# 503-WS2811-Multi_RV100.net
KiCad netlist of a schematic drawn in EAGLE
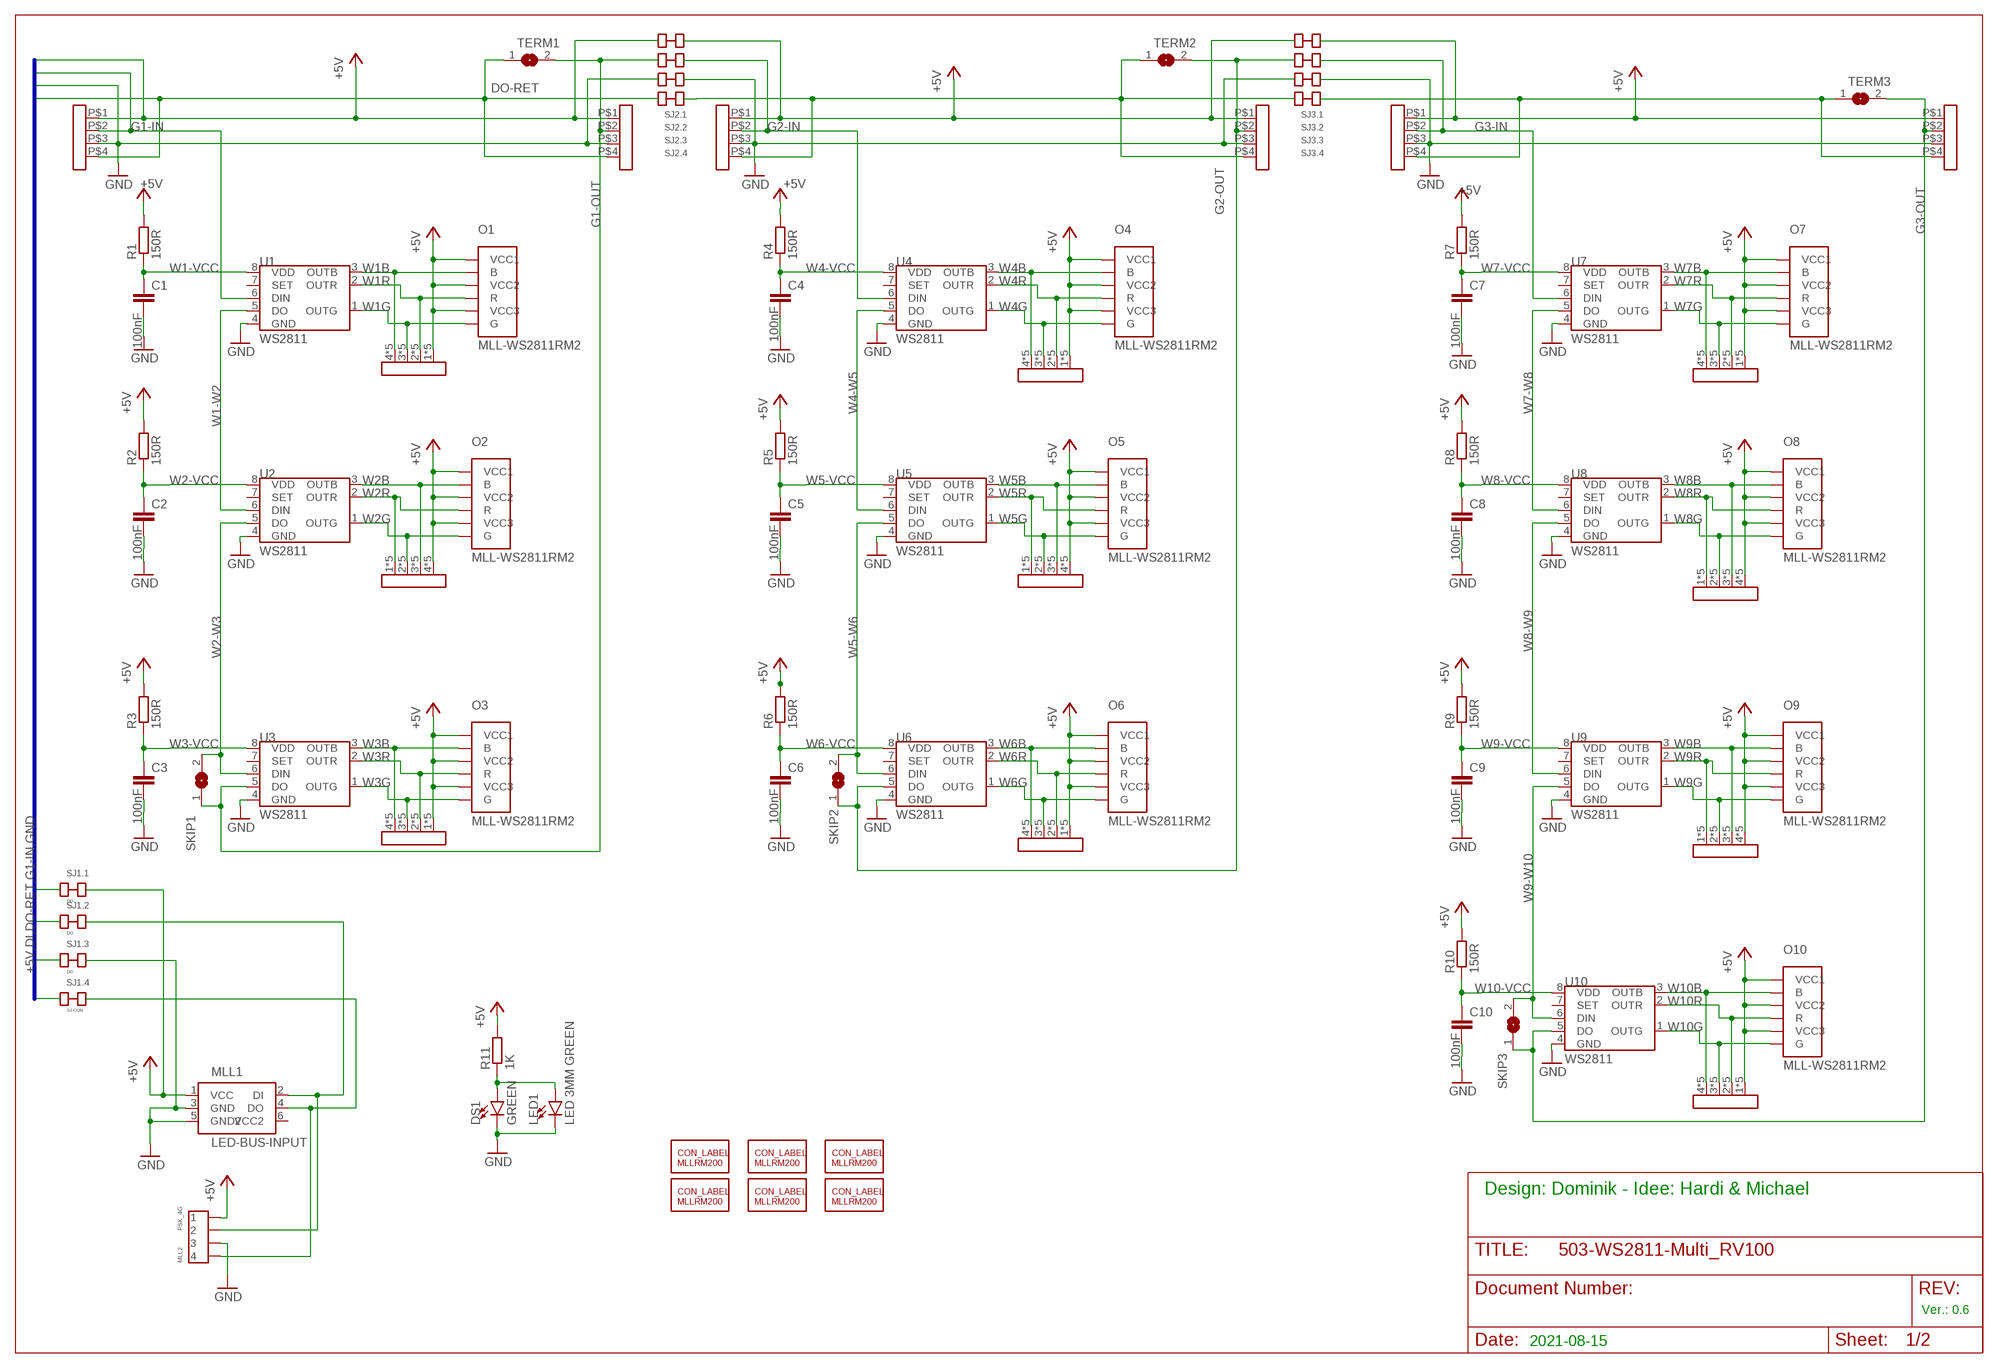
[diagram p0: schematic, sheet 1]
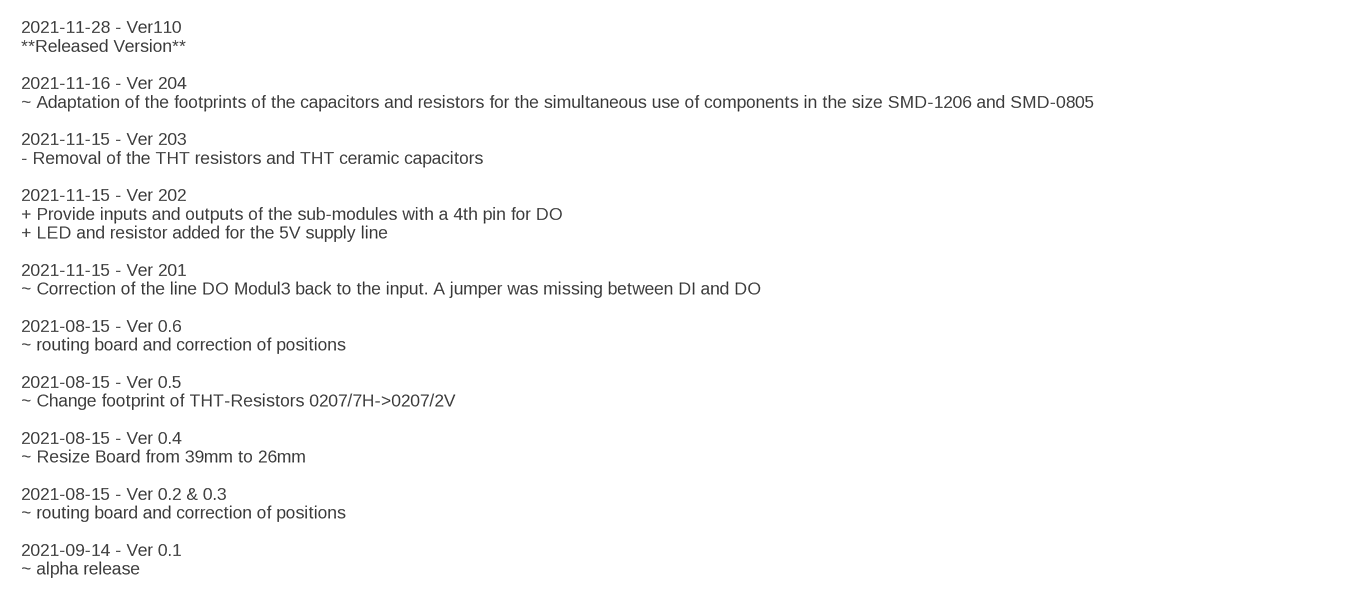
[diagram p1: schematic, sheet 2]

(export (version "E")
  (design (tool "Eeschema 10.0.6"))
  (components
    (comp (ref "C1")
      (value "100nF")
      (footprint "eagle-import:C1206")
      (libsource (lib "eagle-import") (part "C-EUC1206"))
    )
    (comp (ref "C2")
      (value "100nF")
      (footprint "eagle-import:C1206")
      (libsource (lib "eagle-import") (part "C-EUC1206"))
    )
    (comp (ref "C3")
      (value "100nF")
      (footprint "eagle-import:C1206")
      (libsource (lib "eagle-import") (part "C-EUC1206"))
    )
    (comp (ref "C4")
      (value "100nF")
      (footprint "eagle-import:C1206")
      (libsource (lib "eagle-import") (part "C-EUC1206"))
    )
    (comp (ref "C5")
      (value "100nF")
      (footprint "eagle-import:C1206")
      (libsource (lib "eagle-import") (part "C-EUC1206"))
    )
    (comp (ref "C6")
      (value "100nF")
      (footprint "eagle-import:C1206")
      (libsource (lib "eagle-import") (part "C-EUC1206"))
    )
    (comp (ref "C7")
      (value "100nF")
      (footprint "eagle-import:C1206")
      (libsource (lib "eagle-import") (part "C-EUC1206"))
    )
    (comp (ref "C8")
      (value "100nF")
      (footprint "eagle-import:C1206")
      (libsource (lib "eagle-import") (part "C-EUC1206"))
    )
    (comp (ref "C9")
      (value "100nF")
      (footprint "eagle-import:C1206")
      (libsource (lib "eagle-import") (part "C-EUC1206"))
    )
    (comp (ref "C10")
      (value "100nF")
      (footprint "eagle-import:C1206")
      (libsource (lib "eagle-import") (part "C-EUC1206"))
    )
    (comp (ref "DS1")
      (value "GREEN")
      (footprint "eagle-import:LED-1206")
      (libsource (lib "eagle-import") (part "LED-GREEN1206"))
    )
    (comp (ref "IN")
      (value "4XRM254")
      (footprint "eagle-import:4XRM254")
      (libsource (lib "eagle-import") (part "4XRM254"))
    )
    (comp (ref "LED1")
      (value "LED 3MM GREEN")
      (footprint "eagle-import:LED_3MM")
      (libsource (lib "eagle-import") (part "LED3MM"))
    )
    (comp (ref "M1_IN")
      (value "4XRM254")
      (footprint "eagle-import:4XRM254")
      (libsource (lib "eagle-import") (part "4XRM254"))
    )
    (comp (ref "M1_OUT")
      (value "4XRM254")
      (footprint "eagle-import:4XRM254")
      (libsource (lib "eagle-import") (part "4XRM254"))
    )
    (comp (ref "M2_IN")
      (value "4XRM254")
      (footprint "eagle-import:4XRM254")
      (libsource (lib "eagle-import") (part "4XRM254"))
    )
    (comp (ref "M2_OUT")
      (value "4XRM254")
      (footprint "eagle-import:4XRM254")
      (libsource (lib "eagle-import") (part "4XRM254"))
    )
    (comp (ref "MLL1")
      (value "LED-BUS-INPUT")
      (footprint "eagle-import:IDC6")
      (libsource (lib "eagle-import") (part "LED-BUS-INPUT"))
    )
    (comp (ref "MLL2")
      (value "PSK_4G")
      (footprint "eagle-import:PSSG4")
      (libsource (lib "eagle-import") (part "PSK_4G"))
    )
    (comp (ref "O1")
      (value "MLL-WS2811RM2")
      (footprint "eagle-import:MLL-WS2811-RM2")
      (libsource (lib "eagle-import") (part "MLL-WS2811RM2"))
    )
    (comp (ref "O2")
      (value "MLL-WS2811RM2")
      (footprint "eagle-import:MLL-WS2811-RM2")
      (libsource (lib "eagle-import") (part "MLL-WS2811RM2"))
    )
    (comp (ref "O3")
      (value "MLL-WS2811RM2")
      (footprint "eagle-import:MLL-WS2811-RM2")
      (libsource (lib "eagle-import") (part "MLL-WS2811RM2"))
    )
    (comp (ref "O4")
      (value "MLL-WS2811RM2")
      (footprint "eagle-import:MLL-WS2811-RM2")
      (libsource (lib "eagle-import") (part "MLL-WS2811RM2"))
    )
    (comp (ref "O5")
      (value "MLL-WS2811RM2")
      (footprint "eagle-import:MLL-WS2811-RM2")
      (libsource (lib "eagle-import") (part "MLL-WS2811RM2"))
    )
    (comp (ref "O6")
      (value "MLL-WS2811RM2")
      (footprint "eagle-import:MLL-WS2811-RM2")
      (libsource (lib "eagle-import") (part "MLL-WS2811RM2"))
    )
    (comp (ref "O7")
      (value "MLL-WS2811RM2")
      (footprint "eagle-import:MLL-WS2811-RM2")
      (libsource (lib "eagle-import") (part "MLL-WS2811RM2"))
    )
    (comp (ref "O8")
      (value "MLL-WS2811RM2")
      (footprint "eagle-import:MLL-WS2811-RM2")
      (libsource (lib "eagle-import") (part "MLL-WS2811RM2"))
    )
    (comp (ref "O9")
      (value "MLL-WS2811RM2")
      (footprint "eagle-import:MLL-WS2811-RM2")
      (libsource (lib "eagle-import") (part "MLL-WS2811RM2"))
    )
    (comp (ref "O10")
      (value "MLL-WS2811RM2")
      (footprint "eagle-import:MLL-WS2811-RM2")
      (libsource (lib "eagle-import") (part "MLL-WS2811RM2"))
    )
    (comp (ref "OUT")
      (value "4XRM254")
      (footprint "eagle-import:4XRM254")
      (libsource (lib "eagle-import") (part "4XRM254"))
    )
    (comp (ref "R1")
      (value "150R")
      (footprint "eagle-import:R1206")
      (libsource (lib "eagle-import") (part "R-EU_R1206"))
    )
    (comp (ref "R2")
      (value "150R")
      (footprint "eagle-import:R1206")
      (libsource (lib "eagle-import") (part "R-EU_R1206"))
    )
    (comp (ref "R3")
      (value "150R")
      (footprint "eagle-import:R1206")
      (libsource (lib "eagle-import") (part "R-EU_R1206"))
    )
    (comp (ref "R4")
      (value "150R")
      (footprint "eagle-import:R1206")
      (libsource (lib "eagle-import") (part "R-EU_R1206"))
    )
    (comp (ref "R5")
      (value "150R")
      (footprint "eagle-import:R1206")
      (libsource (lib "eagle-import") (part "R-EU_R1206"))
    )
    (comp (ref "R6")
      (value "150R")
      (footprint "eagle-import:R1206")
      (libsource (lib "eagle-import") (part "R-EU_R1206"))
    )
    (comp (ref "R7")
      (value "150R")
      (footprint "eagle-import:R1206")
      (libsource (lib "eagle-import") (part "R-EU_R1206"))
    )
    (comp (ref "R8")
      (value "150R")
      (footprint "eagle-import:R1206")
      (libsource (lib "eagle-import") (part "R-EU_R1206"))
    )
    (comp (ref "R9")
      (value "150R")
      (footprint "eagle-import:R1206")
      (libsource (lib "eagle-import") (part "R-EU_R1206"))
    )
    (comp (ref "R10")
      (value "150R")
      (footprint "eagle-import:R1206")
      (libsource (lib "eagle-import") (part "R-EU_R1206"))
    )
    (comp (ref "R11")
      (value "1K")
      (footprint "eagle-import:R1206")
      (libsource (lib "eagle-import") (part "R-EU_R1206"))
    )
    (comp (ref "SJ1.1")
      (value "DO")
      (footprint "eagle-import:SJ-CON")
      (libsource (lib "eagle-import") (part "SJ-CON"))
    )
    (comp (ref "SJ1.2")
      (value "DO")
      (footprint "eagle-import:SJ-CON")
      (libsource (lib "eagle-import") (part "SJ-CON"))
    )
    (comp (ref "SJ1.3")
      (value "DO")
      (footprint "eagle-import:SJ-CON")
      (libsource (lib "eagle-import") (part "SJ-CON"))
    )
    (comp (ref "SJ1.4")
      (value "SJ-CON")
      (footprint "eagle-import:SJ-CON")
      (libsource (lib "eagle-import") (part "SJ-CON"))
    )
    (comp (ref "SJ2.1")
      (value "SJ-CON")
      (footprint "eagle-import:SJ-CON")
      (libsource (lib "eagle-import") (part "SJ-CON"))
    )
    (comp (ref "SJ2.2")
      (value "SJ-CON")
      (footprint "eagle-import:SJ-CON")
      (libsource (lib "eagle-import") (part "SJ-CON"))
    )
    (comp (ref "SJ2.3")
      (value "SJ-CON")
      (footprint "eagle-import:SJ-CON")
      (libsource (lib "eagle-import") (part "SJ-CON"))
    )
    (comp (ref "SJ2.4")
      (value "SJ-CON")
      (footprint "eagle-import:SJ-CON")
      (libsource (lib "eagle-import") (part "SJ-CON"))
    )
    (comp (ref "SJ3.1")
      (value "SJ-CON")
      (footprint "eagle-import:SJ-CON")
      (libsource (lib "eagle-import") (part "SJ-CON"))
    )
    (comp (ref "SJ3.2")
      (value "SJ-CON")
      (footprint "eagle-import:SJ-CON")
      (libsource (lib "eagle-import") (part "SJ-CON"))
    )
    (comp (ref "SJ3.3")
      (value "SJ-CON")
      (footprint "eagle-import:SJ-CON")
      (libsource (lib "eagle-import") (part "SJ-CON"))
    )
    (comp (ref "SJ3.4")
      (value "SJ-CON")
      (footprint "eagle-import:SJ-CON")
      (libsource (lib "eagle-import") (part "SJ-CON"))
    )
    (comp (ref "SKIP1")
      (value "SJ")
      (footprint "eagle-import:SJ")
      (libsource (lib "eagle-import") (part "SJ"))
    )
    (comp (ref "SKIP2")
      (value "SJ")
      (footprint "eagle-import:SJ")
      (libsource (lib "eagle-import") (part "SJ"))
    )
    (comp (ref "SKIP3")
      (value "SJ")
      (footprint "eagle-import:SJ")
      (libsource (lib "eagle-import") (part "SJ"))
    )
    (comp (ref "TERM1")
      (value "SJ")
      (footprint "eagle-import:SJ")
      (libsource (lib "eagle-import") (part "SJ"))
    )
    (comp (ref "TERM2")
      (value "SJ")
      (footprint "eagle-import:SJ")
      (libsource (lib "eagle-import") (part "SJ"))
    )
    (comp (ref "TERM3")
      (value "SJ")
      (footprint "eagle-import:SJ")
      (libsource (lib "eagle-import") (part "SJ"))
    )
    (comp (ref "U$1")
      (value "CON-LABEL_MLLRM200_2RGB_M")
      (footprint "eagle-import:CON-LABEL_MLLRM200_RGB_M")
      (libsource (lib "eagle-import") (part "CON-LABEL_MLLRM200_2RGB_M"))
    )
    (comp (ref "U$2")
      (value "CON-LABEL_MLLRM200_3")
      (footprint "eagle-import:CON-LABEL_MLLRM200_3")
      (libsource (lib "eagle-import") (part "CON-LABEL_MLLRM200_3"))
    )
    (comp (ref "U$3")
      (value "CON-LABEL_MLLRM200_2RGB_M")
      (footprint "eagle-import:CON-LABEL_MLLRM200_RGB_M")
      (libsource (lib "eagle-import") (part "CON-LABEL_MLLRM200_2RGB_M"))
    )
    (comp (ref "U$4")
      (value "CON-LABEL_MLLRM200_2RGB_M")
      (footprint "eagle-import:CON-LABEL_MLLRM200_RGB_M")
      (libsource (lib "eagle-import") (part "CON-LABEL_MLLRM200_2RGB_M"))
    )
    (comp (ref "U$5")
      (value "CON-LABEL_MLLRM200_2RGB")
      (footprint "eagle-import:CON-LABEL_MLLRM200_RGB")
      (libsource (lib "eagle-import") (part "CON-LABEL_MLLRM200_2RGB"))
    )
    (comp (ref "U$6")
      (value "CON-LABEL_MLLRM200_3")
      (footprint "eagle-import:CON-LABEL_MLLRM200_3")
      (libsource (lib "eagle-import") (part "CON-LABEL_MLLRM200_3"))
    )
    (comp (ref "U$7")
      (value "4XRM200LONG-NOH_DOUBLE")
      (footprint "eagle-import:4XRM200LONG_NOH_DOUBLE")
      (libsource (lib "eagle-import") (part "4XRM200LONG-NOH_DOUBLE"))
    )
    (comp (ref "U$8")
      (value "4XRM200LONG-NOH_DOUBLE")
      (footprint "eagle-import:4XRM200LONG_NOH_DOUBLE")
      (libsource (lib "eagle-import") (part "4XRM200LONG-NOH_DOUBLE"))
    )
    (comp (ref "U$9")
      (value "4XRM200LONG-NOH_DOUBLE")
      (footprint "eagle-import:4XRM200LONG_NOH_DOUBLE")
      (libsource (lib "eagle-import") (part "4XRM200LONG-NOH_DOUBLE"))
    )
    (comp (ref "U$14")
      (value "4XRM200LONG-NOH_DOUBLE")
      (footprint "eagle-import:4XRM200LONG_NOH_DOUBLE")
      (libsource (lib "eagle-import") (part "4XRM200LONG-NOH_DOUBLE"))
    )
    (comp (ref "U$15")
      (value "4XRM200LONG-NOH_DOUBLE")
      (footprint "eagle-import:4XRM200LONG_NOH_DOUBLE")
      (libsource (lib "eagle-import") (part "4XRM200LONG-NOH_DOUBLE"))
    )
    (comp (ref "U$16")
      (value "4XRM200LONG-NOH_DOUBLE")
      (footprint "eagle-import:4XRM200LONG_NOH_DOUBLE")
      (libsource (lib "eagle-import") (part "4XRM200LONG-NOH_DOUBLE"))
    )
    (comp (ref "U$17")
      (value "4XRM200LONG-NOH_DOUBLE")
      (footprint "eagle-import:4XRM200LONG_NOH_DOUBLE")
      (libsource (lib "eagle-import") (part "4XRM200LONG-NOH_DOUBLE"))
    )
    (comp (ref "U$18")
      (value "4XRM200LONG-NOH_DOUBLE")
      (footprint "eagle-import:4XRM200LONG_NOH_DOUBLE")
      (libsource (lib "eagle-import") (part "4XRM200LONG-NOH_DOUBLE"))
    )
    (comp (ref "U$19")
      (value "4XRM200LONG-NOH_DOUBLE")
      (footprint "eagle-import:4XRM200LONG_NOH_DOUBLE")
      (libsource (lib "eagle-import") (part "4XRM200LONG-NOH_DOUBLE"))
    )
    (comp (ref "U$20")
      (value "4XRM200LONG-NOH_DOUBLE")
      (footprint "eagle-import:4XRM200LONG_NOH_DOUBLE")
      (libsource (lib "eagle-import") (part "4XRM200LONG-NOH_DOUBLE"))
    )
    (comp (ref "U1")
      (value "WS2811")
      (footprint "eagle-import:SOP8")
      (libsource (lib "eagle-import") (part "WS2811-ICSOP8"))
    )
    (comp (ref "U2")
      (value "WS2811")
      (footprint "eagle-import:SOP8")
      (libsource (lib "eagle-import") (part "WS2811-ICSOP8"))
    )
    (comp (ref "U3")
      (value "WS2811")
      (footprint "eagle-import:SOP8")
      (libsource (lib "eagle-import") (part "WS2811-ICSOP8"))
    )
    (comp (ref "U4")
      (value "WS2811")
      (footprint "eagle-import:SOP8")
      (libsource (lib "eagle-import") (part "WS2811-ICSOP8"))
    )
    (comp (ref "U5")
      (value "WS2811")
      (footprint "eagle-import:SOP8")
      (libsource (lib "eagle-import") (part "WS2811-ICSOP8"))
    )
    (comp (ref "U6")
      (value "WS2811")
      (footprint "eagle-import:SOP8")
      (libsource (lib "eagle-import") (part "WS2811-ICSOP8"))
    )
    (comp (ref "U7")
      (value "WS2811")
      (footprint "eagle-import:SOP8")
      (libsource (lib "eagle-import") (part "WS2811-ICSOP8"))
    )
    (comp (ref "U8")
      (value "WS2811")
      (footprint "eagle-import:SOP8")
      (libsource (lib "eagle-import") (part "WS2811-ICSOP8"))
    )
    (comp (ref "U9")
      (value "WS2811")
      (footprint "eagle-import:SOP8")
      (libsource (lib "eagle-import") (part "WS2811-ICSOP8"))
    )
    (comp (ref "U10")
      (value "WS2811")
      (footprint "eagle-import:SOP8")
      (libsource (lib "eagle-import") (part "WS2811-ICSOP8"))
    )
  )
  (nets
    (net (code "2") (name "+5V") (class "Default")
      (node (ref "IN") (pin "P$1") (pinfunction "P$1_P$1") (pintype "bidirectional"))
      (node (ref "M1_IN") (pin "P$1") (pinfunction "P$1_P$1") (pintype "bidirectional"))
      (node (ref "M1_OUT") (pin "P$1") (pinfunction "P$1_P$1") (pintype "bidirectional"))
      (node (ref "M2_IN") (pin "P$1") (pinfunction "P$1_P$1") (pintype "bidirectional"))
      (node (ref "M2_OUT") (pin "P$1") (pinfunction "P$1_P$1") (pintype "bidirectional"))
      (node (ref "MLL1") (pin "1") (pinfunction "VCC_1") (pintype "power_in"))
      (node (ref "MLL2") (pin "P$1") (pinfunction "1_P$1") (pintype "bidirectional"))
      (node (ref "O1") (pin "VCC1") (pinfunction "VCC1_VCC1") (pintype "bidirectional"))
      (node (ref "O1") (pin "VCC2") (pinfunction "VCC2_VCC2") (pintype "bidirectional"))
      (node (ref "O1") (pin "VCC3") (pinfunction "VCC3_VCC3") (pintype "bidirectional"))
      (node (ref "O10") (pin "VCC1") (pinfunction "VCC1_VCC1") (pintype "bidirectional"))
      (node (ref "O10") (pin "VCC2") (pinfunction "VCC2_VCC2") (pintype "bidirectional"))
      (node (ref "O10") (pin "VCC3") (pinfunction "VCC3_VCC3") (pintype "bidirectional"))
      (node (ref "O2") (pin "VCC1") (pinfunction "VCC1_VCC1") (pintype "bidirectional"))
      (node (ref "O2") (pin "VCC2") (pinfunction "VCC2_VCC2") (pintype "bidirectional"))
      (node (ref "O2") (pin "VCC3") (pinfunction "VCC3_VCC3") (pintype "bidirectional"))
      (node (ref "O3") (pin "VCC1") (pinfunction "VCC1_VCC1") (pintype "bidirectional"))
      (node (ref "O3") (pin "VCC2") (pinfunction "VCC2_VCC2") (pintype "bidirectional"))
      (node (ref "O3") (pin "VCC3") (pinfunction "VCC3_VCC3") (pintype "bidirectional"))
      (node (ref "O4") (pin "VCC1") (pinfunction "VCC1_VCC1") (pintype "bidirectional"))
      (node (ref "O4") (pin "VCC2") (pinfunction "VCC2_VCC2") (pintype "bidirectional"))
      (node (ref "O4") (pin "VCC3") (pinfunction "VCC3_VCC3") (pintype "bidirectional"))
      (node (ref "O5") (pin "VCC1") (pinfunction "VCC1_VCC1") (pintype "bidirectional"))
      (node (ref "O5") (pin "VCC2") (pinfunction "VCC2_VCC2") (pintype "bidirectional"))
      (node (ref "O5") (pin "VCC3") (pinfunction "VCC3_VCC3") (pintype "bidirectional"))
      (node (ref "O6") (pin "VCC1") (pinfunction "VCC1_VCC1") (pintype "bidirectional"))
      (node (ref "O6") (pin "VCC2") (pinfunction "VCC2_VCC2") (pintype "bidirectional"))
      (node (ref "O6") (pin "VCC3") (pinfunction "VCC3_VCC3") (pintype "bidirectional"))
      (node (ref "O7") (pin "VCC1") (pinfunction "VCC1_VCC1") (pintype "bidirectional"))
      (node (ref "O7") (pin "VCC2") (pinfunction "VCC2_VCC2") (pintype "bidirectional"))
      (node (ref "O7") (pin "VCC3") (pinfunction "VCC3_VCC3") (pintype "bidirectional"))
      (node (ref "O8") (pin "VCC1") (pinfunction "VCC1_VCC1") (pintype "bidirectional"))
      (node (ref "O8") (pin "VCC2") (pinfunction "VCC2_VCC2") (pintype "bidirectional"))
      (node (ref "O8") (pin "VCC3") (pinfunction "VCC3_VCC3") (pintype "bidirectional"))
      (node (ref "O9") (pin "VCC1") (pinfunction "VCC1_VCC1") (pintype "bidirectional"))
      (node (ref "O9") (pin "VCC2") (pinfunction "VCC2_VCC2") (pintype "bidirectional"))
      (node (ref "O9") (pin "VCC3") (pinfunction "VCC3_VCC3") (pintype "bidirectional"))
      (node (ref "OUT") (pin "P$1") (pinfunction "P$1_P$1") (pintype "bidirectional"))
      (node (ref "R1") (pin "2") (pinfunction "2_2") (pintype "passive"))
      (node (ref "R10") (pin "2") (pinfunction "2_2") (pintype "passive"))
      (node (ref "R11") (pin "2") (pinfunction "2_2") (pintype "passive"))
      (node (ref "R2") (pin "2") (pinfunction "2_2") (pintype "passive"))
      (node (ref "R3") (pin "2") (pinfunction "2_2") (pintype "passive"))
      (node (ref "R4") (pin "2") (pinfunction "2_2") (pintype "passive"))
      (node (ref "R5") (pin "2") (pinfunction "2_2") (pintype "passive"))
      (node (ref "R6") (pin "2") (pinfunction "2_2") (pintype "passive"))
      (node (ref "R7") (pin "2") (pinfunction "2_2") (pintype "passive"))
      (node (ref "R8") (pin "2") (pinfunction "2_2") (pintype "passive"))
      (node (ref "R9") (pin "2") (pinfunction "2_2") (pintype "passive"))
      (node (ref "SJ1.1") (pin "P$1") (pinfunction "P$1_P$1") (pintype "bidirectional"))
      (node (ref "SJ1.1") (pin "P$2") (pinfunction "P$2_P$2") (pintype "bidirectional"))
      (node (ref "SJ2.1") (pin "P$1") (pinfunction "P$1_P$1") (pintype "bidirectional"))
      (node (ref "SJ2.1") (pin "P$2") (pinfunction "P$2_P$2") (pintype "bidirectional"))
      (node (ref "SJ3.1") (pin "P$1") (pinfunction "P$1_P$1") (pintype "bidirectional"))
      (node (ref "SJ3.1") (pin "P$2") (pinfunction "P$2_P$2") (pintype "bidirectional"))
      (node (ref "U$14") (pin "1") (pinfunction "P$1_1") (pintype "bidirectional"))
      (node (ref "U$14") (pin "11") (pinfunction "P$1_11") (pintype "bidirectional"))
      (node (ref "U$14") (pin "12") (pinfunction "P$1_12") (pintype "bidirectional"))
      (node (ref "U$14") (pin "13") (pinfunction "P$1_13") (pintype "bidirectional"))
      (node (ref "U$14") (pin "1B") (pinfunction "P$1_1B") (pintype "bidirectional"))
      (node (ref "U$15") (pin "4") (pinfunction "P$4_4") (pintype "bidirectional"))
      (node (ref "U$15") (pin "41") (pinfunction "P$4_41") (pintype "bidirectional"))
      (node (ref "U$15") (pin "42") (pinfunction "P$4_42") (pintype "bidirectional"))
      (node (ref "U$15") (pin "43") (pinfunction "P$4_43") (pintype "bidirectional"))
      (node (ref "U$15") (pin "4B") (pinfunction "P$4_4B") (pintype "bidirectional"))
      (node (ref "U$16") (pin "1") (pinfunction "P$1_1") (pintype "bidirectional"))
      (node (ref "U$16") (pin "11") (pinfunction "P$1_11") (pintype "bidirectional"))
      (node (ref "U$16") (pin "12") (pinfunction "P$1_12") (pintype "bidirectional"))
      (node (ref "U$16") (pin "13") (pinfunction "P$1_13") (pintype "bidirectional"))
      (node (ref "U$16") (pin "1B") (pinfunction "P$1_1B") (pintype "bidirectional"))
      (node (ref "U$17") (pin "1") (pinfunction "P$1_1") (pintype "bidirectional"))
      (node (ref "U$17") (pin "11") (pinfunction "P$1_11") (pintype "bidirectional"))
      (node (ref "U$17") (pin "12") (pinfunction "P$1_12") (pintype "bidirectional"))
      (node (ref "U$17") (pin "13") (pinfunction "P$1_13") (pintype "bidirectional"))
      (node (ref "U$17") (pin "1B") (pinfunction "P$1_1B") (pintype "bidirectional"))
      (node (ref "U$18") (pin "4") (pinfunction "P$4_4") (pintype "bidirectional"))
      (node (ref "U$18") (pin "41") (pinfunction "P$4_41") (pintype "bidirectional"))
      (node (ref "U$18") (pin "42") (pinfunction "P$4_42") (pintype "bidirectional"))
      (node (ref "U$18") (pin "43") (pinfunction "P$4_43") (pintype "bidirectional"))
      (node (ref "U$18") (pin "4B") (pinfunction "P$4_4B") (pintype "bidirectional"))
      (node (ref "U$19") (pin "4") (pinfunction "P$4_4") (pintype "bidirectional"))
      (node (ref "U$19") (pin "41") (pinfunction "P$4_41") (pintype "bidirectional"))
      (node (ref "U$19") (pin "42") (pinfunction "P$4_42") (pintype "bidirectional"))
      (node (ref "U$19") (pin "43") (pinfunction "P$4_43") (pintype "bidirectional"))
      (node (ref "U$19") (pin "4B") (pinfunction "P$4_4B") (pintype "bidirectional"))
      (node (ref "U$20") (pin "1") (pinfunction "P$1_1") (pintype "bidirectional"))
      (node (ref "U$20") (pin "11") (pinfunction "P$1_11") (pintype "bidirectional"))
      (node (ref "U$20") (pin "12") (pinfunction "P$1_12") (pintype "bidirectional"))
      (node (ref "U$20") (pin "13") (pinfunction "P$1_13") (pintype "bidirectional"))
      (node (ref "U$20") (pin "1B") (pinfunction "P$1_1B") (pintype "bidirectional"))
      (node (ref "U$7") (pin "1") (pinfunction "P$1_1") (pintype "bidirectional"))
      (node (ref "U$7") (pin "11") (pinfunction "P$1_11") (pintype "bidirectional"))
      (node (ref "U$7") (pin "12") (pinfunction "P$1_12") (pintype "bidirectional"))
      (node (ref "U$7") (pin "13") (pinfunction "P$1_13") (pintype "bidirectional"))
      (node (ref "U$7") (pin "1B") (pinfunction "P$1_1B") (pintype "bidirectional"))
      (node (ref "U$8") (pin "4") (pinfunction "P$4_4") (pintype "bidirectional"))
      (node (ref "U$8") (pin "41") (pinfunction "P$4_41") (pintype "bidirectional"))
      (node (ref "U$8") (pin "42") (pinfunction "P$4_42") (pintype "bidirectional"))
      (node (ref "U$8") (pin "43") (pinfunction "P$4_43") (pintype "bidirectional"))
      (node (ref "U$8") (pin "4B") (pinfunction "P$4_4B") (pintype "bidirectional"))
      (node (ref "U$9") (pin "1") (pinfunction "P$1_1") (pintype "bidirectional"))
      (node (ref "U$9") (pin "11") (pinfunction "P$1_11") (pintype "bidirectional"))
      (node (ref "U$9") (pin "12") (pinfunction "P$1_12") (pintype "bidirectional"))
      (node (ref "U$9") (pin "13") (pinfunction "P$1_13") (pintype "bidirectional"))
      (node (ref "U$9") (pin "1B") (pinfunction "P$1_1B") (pintype "bidirectional"))
    )
    (net (code "4") (name "DO-RET") (class "Default")
      (node (ref "M1_IN") (pin "P$4") (pinfunction "P$4_P$4") (pintype "bidirectional"))
      (node (ref "M1_OUT") (pin "P$4") (pinfunction "P$4_P$4") (pintype "bidirectional"))
      (node (ref "SJ1.4") (pin "P$1") (pinfunction "P$1_P$1") (pintype "bidirectional"))
      (node (ref "SJ2.4") (pin "P$1") (pinfunction "P$1_P$1") (pintype "bidirectional"))
      (node (ref "TERM1") (pin "1") (pinfunction "1_1") (pintype "passive"))
    )
    (net (code "5") (name "G1-IN") (class "Default")
      (node (ref "M1_IN") (pin "P$2") (pinfunction "P$2_P$2") (pintype "bidirectional"))
      (node (ref "SJ1.2") (pin "P$1") (pinfunction "P$1_P$1") (pintype "bidirectional"))
      (node (ref "U1") (pin "6") (pinfunction "DIN_6") (pintype "input"))
    )
    (net (code "6") (name "G1-OUT") (class "Default")
      (node (ref "M1_OUT") (pin "P$2") (pinfunction "P$2_P$2") (pintype "bidirectional"))
      (node (ref "SJ2.2") (pin "P$1") (pinfunction "P$1_P$1") (pintype "bidirectional"))
      (node (ref "SKIP1") (pin "1") (pinfunction "1_1") (pintype "passive"))
      (node (ref "TERM1") (pin "2") (pinfunction "2_2") (pintype "passive"))
      (node (ref "U3") (pin "5") (pinfunction "DO_5") (pintype "output"))
    )
    (net (code "7") (name "G2-IN") (class "Default")
      (node (ref "M2_IN") (pin "P$2") (pinfunction "P$2_P$2") (pintype "bidirectional"))
      (node (ref "SJ2.2") (pin "P$2") (pinfunction "P$2_P$2") (pintype "bidirectional"))
      (node (ref "U4") (pin "6") (pinfunction "DIN_6") (pintype "input"))
    )
    (net (code "8") (name "G2-OUT") (class "Default")
      (node (ref "M2_OUT") (pin "P$2") (pinfunction "P$2_P$2") (pintype "bidirectional"))
      (node (ref "SJ3.2") (pin "P$1") (pinfunction "P$1_P$1") (pintype "bidirectional"))
      (node (ref "SKIP2") (pin "1") (pinfunction "1_1") (pintype "passive"))
      (node (ref "TERM2") (pin "2") (pinfunction "2_2") (pintype "passive"))
      (node (ref "U6") (pin "5") (pinfunction "DO_5") (pintype "output"))
    )
    (net (code "9") (name "G3-IN") (class "Default")
      (node (ref "IN") (pin "P$2") (pinfunction "P$2_P$2") (pintype "bidirectional"))
      (node (ref "SJ3.2") (pin "P$2") (pinfunction "P$2_P$2") (pintype "bidirectional"))
      (node (ref "U7") (pin "6") (pinfunction "DIN_6") (pintype "input"))
    )
    (net (code "10") (name "G3-OUT") (class "Default")
      (node (ref "OUT") (pin "P$2") (pinfunction "P$2_P$2") (pintype "bidirectional"))
      (node (ref "SKIP3") (pin "1") (pinfunction "1_1") (pintype "passive"))
      (node (ref "TERM3") (pin "2") (pinfunction "2_2") (pintype "passive"))
      (node (ref "U10") (pin "5") (pinfunction "DO_5") (pintype "output"))
    )
    (net (code "11") (name "GND") (class "Default")
      (node (ref "C1") (pin "2") (pinfunction "2_2") (pintype "passive"))
      (node (ref "C10") (pin "2") (pinfunction "2_2") (pintype "passive"))
      (node (ref "C2") (pin "2") (pinfunction "2_2") (pintype "passive"))
      (node (ref "C3") (pin "2") (pinfunction "2_2") (pintype "passive"))
      (node (ref "C4") (pin "2") (pinfunction "2_2") (pintype "passive"))
      (node (ref "C5") (pin "2") (pinfunction "2_2") (pintype "passive"))
      (node (ref "C6") (pin "2") (pinfunction "2_2") (pintype "passive"))
      (node (ref "C7") (pin "2") (pinfunction "2_2") (pintype "passive"))
      (node (ref "C8") (pin "2") (pinfunction "2_2") (pintype "passive"))
      (node (ref "C9") (pin "2") (pinfunction "2_2") (pintype "passive"))
      (node (ref "DS1") (pin "C") (pinfunction "C_C") (pintype "passive"))
      (node (ref "IN") (pin "P$3") (pinfunction "P$3_P$3") (pintype "bidirectional"))
      (node (ref "LED1") (pin "K") (pinfunction "C_K") (pintype "passive"))
      (node (ref "M1_IN") (pin "P$3") (pinfunction "P$3_P$3") (pintype "bidirectional"))
      (node (ref "M1_OUT") (pin "P$3") (pinfunction "P$3_P$3") (pintype "bidirectional"))
      (node (ref "M2_IN") (pin "P$3") (pinfunction "P$3_P$3") (pintype "bidirectional"))
      (node (ref "M2_OUT") (pin "P$3") (pinfunction "P$3_P$3") (pintype "bidirectional"))
      (node (ref "MLL1") (pin "3") (pinfunction "GND_3") (pintype "power_in"))
      (node (ref "MLL1") (pin "5") (pinfunction "GND2_5") (pintype "power_in"))
      (node (ref "MLL2") (pin "P$3") (pinfunction "3_P$3") (pintype "bidirectional"))
      (node (ref "OUT") (pin "P$3") (pinfunction "P$3_P$3") (pintype "bidirectional"))
      (node (ref "SJ1.3") (pin "P$1") (pinfunction "P$1_P$1") (pintype "bidirectional"))
      (node (ref "SJ1.3") (pin "P$2") (pinfunction "P$2_P$2") (pintype "bidirectional"))
      (node (ref "SJ2.3") (pin "P$1") (pinfunction "P$1_P$1") (pintype "bidirectional"))
      (node (ref "SJ2.3") (pin "P$2") (pinfunction "P$2_P$2") (pintype "bidirectional"))
      (node (ref "SJ3.3") (pin "P$1") (pinfunction "P$1_P$1") (pintype "bidirectional"))
      (node (ref "SJ3.3") (pin "P$2") (pinfunction "P$2_P$2") (pintype "bidirectional"))
      (node (ref "U1") (pin "4") (pinfunction "GND_4") (pintype "power_in"))
      (node (ref "U10") (pin "4") (pinfunction "GND_4") (pintype "power_in"))
      (node (ref "U2") (pin "4") (pinfunction "GND_4") (pintype "power_in"))
      (node (ref "U3") (pin "4") (pinfunction "GND_4") (pintype "power_in"))
      (node (ref "U4") (pin "4") (pinfunction "GND_4") (pintype "power_in"))
      (node (ref "U5") (pin "4") (pinfunction "GND_4") (pintype "power_in"))
      (node (ref "U6") (pin "4") (pinfunction "GND_4") (pintype "power_in"))
      (node (ref "U7") (pin "4") (pinfunction "GND_4") (pintype "power_in"))
      (node (ref "U8") (pin "4") (pinfunction "GND_4") (pintype "power_in"))
      (node (ref "U9") (pin "4") (pinfunction "GND_4") (pintype "power_in"))
    )
    (net (code "12") (name "Net-(DS1-PadA)") (class "Default")
      (node (ref "DS1") (pin "A") (pinfunction "A_A") (pintype "passive"))
      (node (ref "LED1") (pin "A") (pinfunction "A_A") (pintype "passive"))
      (node (ref "R11") (pin "1") (pinfunction "1_1") (pintype "passive"))
    )
    (net (code "13") (name "Net-(IN-PadP$4)") (class "Default")
      (node (ref "IN") (pin "P$4") (pinfunction "P$4_P$4") (pintype "bidirectional"))
      (node (ref "OUT") (pin "P$4") (pinfunction "P$4_P$4") (pintype "bidirectional"))
      (node (ref "SJ3.4") (pin "P$2") (pinfunction "P$2_P$2") (pintype "bidirectional"))
      (node (ref "TERM3") (pin "1") (pinfunction "1_1") (pintype "passive"))
    )
    (net (code "14") (name "Net-(M2_IN-PadP$4)") (class "Default")
      (node (ref "M2_IN") (pin "P$4") (pinfunction "P$4_P$4") (pintype "bidirectional"))
      (node (ref "M2_OUT") (pin "P$4") (pinfunction "P$4_P$4") (pintype "bidirectional"))
      (node (ref "SJ2.4") (pin "P$2") (pinfunction "P$2_P$2") (pintype "bidirectional"))
      (node (ref "SJ3.4") (pin "P$1") (pinfunction "P$1_P$1") (pintype "bidirectional"))
      (node (ref "TERM2") (pin "1") (pinfunction "1_1") (pintype "passive"))
    )
    (net (code "15") (name "Net-(MLL1-DI)") (class "Default")
      (node (ref "MLL1") (pin "2") (pinfunction "DI_2") (pintype "input"))
      (node (ref "MLL2") (pin "P$2") (pinfunction "2_P$2") (pintype "bidirectional"))
      (node (ref "SJ1.2") (pin "P$2") (pinfunction "P$2_P$2") (pintype "bidirectional"))
    )
    (net (code "16") (name "Net-(MLL1-DO)") (class "Default")
      (node (ref "MLL1") (pin "4") (pinfunction "DO_4") (pintype "output"))
      (node (ref "MLL2") (pin "P$4") (pinfunction "4_P$4") (pintype "bidirectional"))
      (node (ref "SJ1.4") (pin "P$2") (pinfunction "P$2_P$2") (pintype "bidirectional"))
    )
    (net (code "17") (name "VCC2") (class "Default")
      (node (ref "MLL1") (pin "6") (pinfunction "VCC2_6") (pintype "power_in"))
    )
    (net (code "18") (name "W1-VCC") (class "Default")
      (node (ref "C1") (pin "1") (pinfunction "1_1") (pintype "passive"))
      (node (ref "R1") (pin "1") (pinfunction "1_1") (pintype "passive"))
      (node (ref "U1") (pin "8") (pinfunction "VDD_8") (pintype "power_in"))
    )
    (net (code "19") (name "W1-W2") (class "Default")
      (node (ref "U1") (pin "5") (pinfunction "DO_5") (pintype "output"))
      (node (ref "U2") (pin "6") (pinfunction "DIN_6") (pintype "input"))
    )
    (net (code "20") (name "W1B") (class "Default")
      (node (ref "O1") (pin "B") (pinfunction "B_B") (pintype "bidirectional"))
      (node (ref "U$9") (pin "4") (pinfunction "P$4_4") (pintype "bidirectional"))
      (node (ref "U$9") (pin "41") (pinfunction "P$4_41") (pintype "bidirectional"))
      (node (ref "U$9") (pin "42") (pinfunction "P$4_42") (pintype "bidirectional"))
      (node (ref "U$9") (pin "43") (pinfunction "P$4_43") (pintype "bidirectional"))
      (node (ref "U$9") (pin "4B") (pinfunction "P$4_4B") (pintype "bidirectional"))
      (node (ref "U1") (pin "3") (pinfunction "OUTB_3") (pintype "open_collector"))
    )
    (net (code "21") (name "W1G") (class "Default")
      (node (ref "O1") (pin "G") (pinfunction "G_G") (pintype "bidirectional"))
      (node (ref "U$9") (pin "3") (pinfunction "P$3_3") (pintype "bidirectional"))
      (node (ref "U$9") (pin "31") (pinfunction "P$3_31") (pintype "bidirectional"))
      (node (ref "U$9") (pin "32") (pinfunction "P$3_32") (pintype "bidirectional"))
      (node (ref "U$9") (pin "33") (pinfunction "P$3_33") (pintype "bidirectional"))
      (node (ref "U$9") (pin "3B") (pinfunction "P$3_3B") (pintype "bidirectional"))
      (node (ref "U1") (pin "1") (pinfunction "OUTG_1") (pintype "open_collector"))
    )
    (net (code "22") (name "W1R") (class "Default")
      (node (ref "O1") (pin "R") (pinfunction "R_R") (pintype "bidirectional"))
      (node (ref "U$9") (pin "2") (pinfunction "P$2_2") (pintype "bidirectional"))
      (node (ref "U$9") (pin "21") (pinfunction "P$2_21") (pintype "bidirectional"))
      (node (ref "U$9") (pin "22") (pinfunction "P$2_22") (pintype "bidirectional"))
      (node (ref "U$9") (pin "23") (pinfunction "P$2_23") (pintype "bidirectional"))
      (node (ref "U$9") (pin "2B") (pinfunction "P$2_2B") (pintype "bidirectional"))
      (node (ref "U1") (pin "2") (pinfunction "OUTR_2") (pintype "open_collector"))
    )
    (net (code "23") (name "W2-VCC") (class "Default")
      (node (ref "C2") (pin "1") (pinfunction "1_1") (pintype "passive"))
      (node (ref "R2") (pin "1") (pinfunction "1_1") (pintype "passive"))
      (node (ref "U2") (pin "8") (pinfunction "VDD_8") (pintype "power_in"))
    )
    (net (code "24") (name "W2-W3") (class "Default")
      (node (ref "SKIP1") (pin "2") (pinfunction "2_2") (pintype "passive"))
      (node (ref "U2") (pin "5") (pinfunction "DO_5") (pintype "output"))
      (node (ref "U3") (pin "6") (pinfunction "DIN_6") (pintype "input"))
    )
    (net (code "25") (name "W2B") (class "Default")
      (node (ref "O2") (pin "B") (pinfunction "B_B") (pintype "bidirectional"))
      (node (ref "U$8") (pin "3") (pinfunction "P$3_3") (pintype "bidirectional"))
      (node (ref "U$8") (pin "31") (pinfunction "P$3_31") (pintype "bidirectional"))
      (node (ref "U$8") (pin "32") (pinfunction "P$3_32") (pintype "bidirectional"))
      (node (ref "U$8") (pin "33") (pinfunction "P$3_33") (pintype "bidirectional"))
      (node (ref "U$8") (pin "3B") (pinfunction "P$3_3B") (pintype "bidirectional"))
      (node (ref "U2") (pin "3") (pinfunction "OUTB_3") (pintype "open_collector"))
    )
    (net (code "26") (name "W2G") (class "Default")
      (node (ref "O2") (pin "G") (pinfunction "G_G") (pintype "bidirectional"))
      (node (ref "U$8") (pin "2") (pinfunction "P$2_2") (pintype "bidirectional"))
      (node (ref "U$8") (pin "21") (pinfunction "P$2_21") (pintype "bidirectional"))
      (node (ref "U$8") (pin "22") (pinfunction "P$2_22") (pintype "bidirectional"))
      (node (ref "U$8") (pin "23") (pinfunction "P$2_23") (pintype "bidirectional"))
      (node (ref "U$8") (pin "2B") (pinfunction "P$2_2B") (pintype "bidirectional"))
      (node (ref "U2") (pin "1") (pinfunction "OUTG_1") (pintype "open_collector"))
    )
    (net (code "27") (name "W2R") (class "Default")
      (node (ref "O2") (pin "R") (pinfunction "R_R") (pintype "bidirectional"))
      (node (ref "U$8") (pin "1") (pinfunction "P$1_1") (pintype "bidirectional"))
      (node (ref "U$8") (pin "11") (pinfunction "P$1_11") (pintype "bidirectional"))
      (node (ref "U$8") (pin "12") (pinfunction "P$1_12") (pintype "bidirectional"))
      (node (ref "U$8") (pin "13") (pinfunction "P$1_13") (pintype "bidirectional"))
      (node (ref "U$8") (pin "1B") (pinfunction "P$1_1B") (pintype "bidirectional"))
      (node (ref "U2") (pin "2") (pinfunction "OUTR_2") (pintype "open_collector"))
    )
    (net (code "28") (name "W3-VCC") (class "Default")
      (node (ref "C3") (pin "1") (pinfunction "1_1") (pintype "passive"))
      (node (ref "R3") (pin "1") (pinfunction "1_1") (pintype "passive"))
      (node (ref "U3") (pin "8") (pinfunction "VDD_8") (pintype "power_in"))
    )
    (net (code "29") (name "W3B") (class "Default")
      (node (ref "O3") (pin "B") (pinfunction "B_B") (pintype "bidirectional"))
      (node (ref "U$7") (pin "4") (pinfunction "P$4_4") (pintype "bidirectional"))
      (node (ref "U$7") (pin "41") (pinfunction "P$4_41") (pintype "bidirectional"))
      (node (ref "U$7") (pin "42") (pinfunction "P$4_42") (pintype "bidirectional"))
      (node (ref "U$7") (pin "43") (pinfunction "P$4_43") (pintype "bidirectional"))
      (node (ref "U$7") (pin "4B") (pinfunction "P$4_4B") (pintype "bidirectional"))
      (node (ref "U3") (pin "3") (pinfunction "OUTB_3") (pintype "open_collector"))
    )
    (net (code "30") (name "W3G") (class "Default")
      (node (ref "O3") (pin "G") (pinfunction "G_G") (pintype "bidirectional"))
      (node (ref "U$7") (pin "3") (pinfunction "P$3_3") (pintype "bidirectional"))
      (node (ref "U$7") (pin "31") (pinfunction "P$3_31") (pintype "bidirectional"))
      (node (ref "U$7") (pin "32") (pinfunction "P$3_32") (pintype "bidirectional"))
      (node (ref "U$7") (pin "33") (pinfunction "P$3_33") (pintype "bidirectional"))
      (node (ref "U$7") (pin "3B") (pinfunction "P$3_3B") (pintype "bidirectional"))
      (node (ref "U3") (pin "1") (pinfunction "OUTG_1") (pintype "open_collector"))
    )
    (net (code "31") (name "W3R") (class "Default")
      (node (ref "O3") (pin "R") (pinfunction "R_R") (pintype "bidirectional"))
      (node (ref "U$7") (pin "2") (pinfunction "P$2_2") (pintype "bidirectional"))
      (node (ref "U$7") (pin "21") (pinfunction "P$2_21") (pintype "bidirectional"))
      (node (ref "U$7") (pin "22") (pinfunction "P$2_22") (pintype "bidirectional"))
      (node (ref "U$7") (pin "23") (pinfunction "P$2_23") (pintype "bidirectional"))
      (node (ref "U$7") (pin "2B") (pinfunction "P$2_2B") (pintype "bidirectional"))
      (node (ref "U3") (pin "2") (pinfunction "OUTR_2") (pintype "open_collector"))
    )
    (net (code "32") (name "W4-VCC") (class "Default")
      (node (ref "C4") (pin "1") (pinfunction "1_1") (pintype "passive"))
      (node (ref "R4") (pin "1") (pinfunction "1_1") (pintype "passive"))
      (node (ref "U4") (pin "8") (pinfunction "VDD_8") (pintype "power_in"))
    )
    (net (code "33") (name "W4-W5") (class "Default")
      (node (ref "U4") (pin "5") (pinfunction "DO_5") (pintype "output"))
      (node (ref "U5") (pin "6") (pinfunction "DIN_6") (pintype "input"))
    )
    (net (code "34") (name "W4B") (class "Default")
      (node (ref "O4") (pin "B") (pinfunction "B_B") (pintype "bidirectional"))
      (node (ref "U$14") (pin "4") (pinfunction "P$4_4") (pintype "bidirectional"))
      (node (ref "U$14") (pin "41") (pinfunction "P$4_41") (pintype "bidirectional"))
      (node (ref "U$14") (pin "42") (pinfunction "P$4_42") (pintype "bidirectional"))
      (node (ref "U$14") (pin "43") (pinfunction "P$4_43") (pintype "bidirectional"))
      (node (ref "U$14") (pin "4B") (pinfunction "P$4_4B") (pintype "bidirectional"))
      (node (ref "U4") (pin "3") (pinfunction "OUTB_3") (pintype "open_collector"))
    )
    (net (code "35") (name "W4G") (class "Default")
      (node (ref "O4") (pin "G") (pinfunction "G_G") (pintype "bidirectional"))
      (node (ref "U$14") (pin "3") (pinfunction "P$3_3") (pintype "bidirectional"))
      (node (ref "U$14") (pin "31") (pinfunction "P$3_31") (pintype "bidirectional"))
      (node (ref "U$14") (pin "32") (pinfunction "P$3_32") (pintype "bidirectional"))
      (node (ref "U$14") (pin "33") (pinfunction "P$3_33") (pintype "bidirectional"))
      (node (ref "U$14") (pin "3B") (pinfunction "P$3_3B") (pintype "bidirectional"))
      (node (ref "U4") (pin "1") (pinfunction "OUTG_1") (pintype "open_collector"))
    )
    (net (code "36") (name "W4R") (class "Default")
      (node (ref "O4") (pin "R") (pinfunction "R_R") (pintype "bidirectional"))
      (node (ref "U$14") (pin "2") (pinfunction "P$2_2") (pintype "bidirectional"))
      (node (ref "U$14") (pin "21") (pinfunction "P$2_21") (pintype "bidirectional"))
      (node (ref "U$14") (pin "22") (pinfunction "P$2_22") (pintype "bidirectional"))
      (node (ref "U$14") (pin "23") (pinfunction "P$2_23") (pintype "bidirectional"))
      (node (ref "U$14") (pin "2B") (pinfunction "P$2_2B") (pintype "bidirectional"))
      (node (ref "U4") (pin "2") (pinfunction "OUTR_2") (pintype "open_collector"))
    )
    (net (code "37") (name "W5-VCC") (class "Default")
      (node (ref "C5") (pin "1") (pinfunction "1_1") (pintype "passive"))
      (node (ref "R5") (pin "1") (pinfunction "1_1") (pintype "passive"))
      (node (ref "U5") (pin "8") (pinfunction "VDD_8") (pintype "power_in"))
    )
    (net (code "38") (name "W5-W6") (class "Default")
      (node (ref "SKIP2") (pin "2") (pinfunction "2_2") (pintype "passive"))
      (node (ref "U5") (pin "5") (pinfunction "DO_5") (pintype "output"))
      (node (ref "U6") (pin "6") (pinfunction "DIN_6") (pintype "input"))
    )
    (net (code "39") (name "W5B") (class "Default")
      (node (ref "O5") (pin "B") (pinfunction "B_B") (pintype "bidirectional"))
      (node (ref "U$15") (pin "3") (pinfunction "P$3_3") (pintype "bidirectional"))
      (node (ref "U$15") (pin "31") (pinfunction "P$3_31") (pintype "bidirectional"))
      (node (ref "U$15") (pin "32") (pinfunction "P$3_32") (pintype "bidirectional"))
      (node (ref "U$15") (pin "33") (pinfunction "P$3_33") (pintype "bidirectional"))
      (node (ref "U$15") (pin "3B") (pinfunction "P$3_3B") (pintype "bidirectional"))
      (node (ref "U5") (pin "3") (pinfunction "OUTB_3") (pintype "open_collector"))
    )
    (net (code "40") (name "W5G") (class "Default")
      (node (ref "O5") (pin "G") (pinfunction "G_G") (pintype "bidirectional"))
      (node (ref "U$15") (pin "2") (pinfunction "P$2_2") (pintype "bidirectional"))
      (node (ref "U$15") (pin "21") (pinfunction "P$2_21") (pintype "bidirectional"))
      (node (ref "U$15") (pin "22") (pinfunction "P$2_22") (pintype "bidirectional"))
      (node (ref "U$15") (pin "23") (pinfunction "P$2_23") (pintype "bidirectional"))
      (node (ref "U$15") (pin "2B") (pinfunction "P$2_2B") (pintype "bidirectional"))
      (node (ref "U5") (pin "1") (pinfunction "OUTG_1") (pintype "open_collector"))
    )
    (net (code "41") (name "W5R") (class "Default")
      (node (ref "O5") (pin "R") (pinfunction "R_R") (pintype "bidirectional"))
      (node (ref "U$15") (pin "1") (pinfunction "P$1_1") (pintype "bidirectional"))
      (node (ref "U$15") (pin "11") (pinfunction "P$1_11") (pintype "bidirectional"))
      (node (ref "U$15") (pin "12") (pinfunction "P$1_12") (pintype "bidirectional"))
      (node (ref "U$15") (pin "13") (pinfunction "P$1_13") (pintype "bidirectional"))
      (node (ref "U$15") (pin "1B") (pinfunction "P$1_1B") (pintype "bidirectional"))
      (node (ref "U5") (pin "2") (pinfunction "OUTR_2") (pintype "open_collector"))
    )
    (net (code "42") (name "W6-VCC") (class "Default")
      (node (ref "C6") (pin "1") (pinfunction "1_1") (pintype "passive"))
      (node (ref "R6") (pin "1") (pinfunction "1_1") (pintype "passive"))
      (node (ref "U6") (pin "8") (pinfunction "VDD_8") (pintype "power_in"))
    )
    (net (code "43") (name "W6B") (class "Default")
      (node (ref "O6") (pin "B") (pinfunction "B_B") (pintype "bidirectional"))
      (node (ref "U$16") (pin "4") (pinfunction "P$4_4") (pintype "bidirectional"))
      (node (ref "U$16") (pin "41") (pinfunction "P$4_41") (pintype "bidirectional"))
      (node (ref "U$16") (pin "42") (pinfunction "P$4_42") (pintype "bidirectional"))
      (node (ref "U$16") (pin "43") (pinfunction "P$4_43") (pintype "bidirectional"))
      (node (ref "U$16") (pin "4B") (pinfunction "P$4_4B") (pintype "bidirectional"))
      (node (ref "U6") (pin "3") (pinfunction "OUTB_3") (pintype "open_collector"))
    )
    (net (code "44") (name "W6G") (class "Default")
      (node (ref "O6") (pin "G") (pinfunction "G_G") (pintype "bidirectional"))
      (node (ref "U$16") (pin "3") (pinfunction "P$3_3") (pintype "bidirectional"))
      (node (ref "U$16") (pin "31") (pinfunction "P$3_31") (pintype "bidirectional"))
      (node (ref "U$16") (pin "32") (pinfunction "P$3_32") (pintype "bidirectional"))
      (node (ref "U$16") (pin "33") (pinfunction "P$3_33") (pintype "bidirectional"))
      (node (ref "U$16") (pin "3B") (pinfunction "P$3_3B") (pintype "bidirectional"))
      (node (ref "U6") (pin "1") (pinfunction "OUTG_1") (pintype "open_collector"))
    )
    (net (code "45") (name "W6R") (class "Default")
      (node (ref "O6") (pin "R") (pinfunction "R_R") (pintype "bidirectional"))
      (node (ref "U$16") (pin "2") (pinfunction "P$2_2") (pintype "bidirectional"))
      (node (ref "U$16") (pin "21") (pinfunction "P$2_21") (pintype "bidirectional"))
      (node (ref "U$16") (pin "22") (pinfunction "P$2_22") (pintype "bidirectional"))
      (node (ref "U$16") (pin "23") (pinfunction "P$2_23") (pintype "bidirectional"))
      (node (ref "U$16") (pin "2B") (pinfunction "P$2_2B") (pintype "bidirectional"))
      (node (ref "U6") (pin "2") (pinfunction "OUTR_2") (pintype "open_collector"))
    )
    (net (code "46") (name "W7-VCC") (class "Default")
      (node (ref "C7") (pin "1") (pinfunction "1_1") (pintype "passive"))
      (node (ref "R7") (pin "1") (pinfunction "1_1") (pintype "passive"))
      (node (ref "U7") (pin "8") (pinfunction "VDD_8") (pintype "power_in"))
    )
    (net (code "47") (name "W7-W8") (class "Default")
      (node (ref "U7") (pin "5") (pinfunction "DO_5") (pintype "output"))
      (node (ref "U8") (pin "6") (pinfunction "DIN_6") (pintype "input"))
    )
    (net (code "48") (name "W7B") (class "Default")
      (node (ref "O7") (pin "B") (pinfunction "B_B") (pintype "bidirectional"))
      (node (ref "U$17") (pin "4") (pinfunction "P$4_4") (pintype "bidirectional"))
      (node (ref "U$17") (pin "41") (pinfunction "P$4_41") (pintype "bidirectional"))
      (node (ref "U$17") (pin "42") (pinfunction "P$4_42") (pintype "bidirectional"))
      (node (ref "U$17") (pin "43") (pinfunction "P$4_43") (pintype "bidirectional"))
      (node (ref "U$17") (pin "4B") (pinfunction "P$4_4B") (pintype "bidirectional"))
      (node (ref "U7") (pin "3") (pinfunction "OUTB_3") (pintype "open_collector"))
    )
    (net (code "49") (name "W7G") (class "Default")
      (node (ref "O7") (pin "G") (pinfunction "G_G") (pintype "bidirectional"))
      (node (ref "U$17") (pin "3") (pinfunction "P$3_3") (pintype "bidirectional"))
      (node (ref "U$17") (pin "31") (pinfunction "P$3_31") (pintype "bidirectional"))
      (node (ref "U$17") (pin "32") (pinfunction "P$3_32") (pintype "bidirectional"))
      (node (ref "U$17") (pin "33") (pinfunction "P$3_33") (pintype "bidirectional"))
      (node (ref "U$17") (pin "3B") (pinfunction "P$3_3B") (pintype "bidirectional"))
      (node (ref "U7") (pin "1") (pinfunction "OUTG_1") (pintype "open_collector"))
    )
    (net (code "50") (name "W7R") (class "Default")
      (node (ref "O7") (pin "R") (pinfunction "R_R") (pintype "bidirectional"))
      (node (ref "U$17") (pin "2") (pinfunction "P$2_2") (pintype "bidirectional"))
      (node (ref "U$17") (pin "21") (pinfunction "P$2_21") (pintype "bidirectional"))
      (node (ref "U$17") (pin "22") (pinfunction "P$2_22") (pintype "bidirectional"))
      (node (ref "U$17") (pin "23") (pinfunction "P$2_23") (pintype "bidirectional"))
      (node (ref "U$17") (pin "2B") (pinfunction "P$2_2B") (pintype "bidirectional"))
      (node (ref "U7") (pin "2") (pinfunction "OUTR_2") (pintype "open_collector"))
    )
    (net (code "51") (name "W8-VCC") (class "Default")
      (node (ref "C8") (pin "1") (pinfunction "1_1") (pintype "passive"))
      (node (ref "R8") (pin "1") (pinfunction "1_1") (pintype "passive"))
      (node (ref "U8") (pin "8") (pinfunction "VDD_8") (pintype "power_in"))
    )
    (net (code "52") (name "W8-W9") (class "Default")
      (node (ref "U8") (pin "5") (pinfunction "DO_5") (pintype "output"))
      (node (ref "U9") (pin "6") (pinfunction "DIN_6") (pintype "input"))
    )
    (net (code "53") (name "W8B") (class "Default")
      (node (ref "O8") (pin "B") (pinfunction "B_B") (pintype "bidirectional"))
      (node (ref "U$18") (pin "3") (pinfunction "P$3_3") (pintype "bidirectional"))
      (node (ref "U$18") (pin "31") (pinfunction "P$3_31") (pintype "bidirectional"))
      (node (ref "U$18") (pin "32") (pinfunction "P$3_32") (pintype "bidirectional"))
      (node (ref "U$18") (pin "33") (pinfunction "P$3_33") (pintype "bidirectional"))
      (node (ref "U$18") (pin "3B") (pinfunction "P$3_3B") (pintype "bidirectional"))
      (node (ref "U8") (pin "3") (pinfunction "OUTB_3") (pintype "open_collector"))
    )
    (net (code "54") (name "W8G") (class "Default")
      (node (ref "O8") (pin "G") (pinfunction "G_G") (pintype "bidirectional"))
      (node (ref "U$18") (pin "2") (pinfunction "P$2_2") (pintype "bidirectional"))
      (node (ref "U$18") (pin "21") (pinfunction "P$2_21") (pintype "bidirectional"))
      (node (ref "U$18") (pin "22") (pinfunction "P$2_22") (pintype "bidirectional"))
      (node (ref "U$18") (pin "23") (pinfunction "P$2_23") (pintype "bidirectional"))
      (node (ref "U$18") (pin "2B") (pinfunction "P$2_2B") (pintype "bidirectional"))
      (node (ref "U8") (pin "1") (pinfunction "OUTG_1") (pintype "open_collector"))
    )
    (net (code "55") (name "W8R") (class "Default")
      (node (ref "O8") (pin "R") (pinfunction "R_R") (pintype "bidirectional"))
      (node (ref "U$18") (pin "1") (pinfunction "P$1_1") (pintype "bidirectional"))
      (node (ref "U$18") (pin "11") (pinfunction "P$1_11") (pintype "bidirectional"))
      (node (ref "U$18") (pin "12") (pinfunction "P$1_12") (pintype "bidirectional"))
      (node (ref "U$18") (pin "13") (pinfunction "P$1_13") (pintype "bidirectional"))
      (node (ref "U$18") (pin "1B") (pinfunction "P$1_1B") (pintype "bidirectional"))
      (node (ref "U8") (pin "2") (pinfunction "OUTR_2") (pintype "open_collector"))
    )
    (net (code "56") (name "W9-VCC") (class "Default")
      (node (ref "C9") (pin "1") (pinfunction "1_1") (pintype "passive"))
      (node (ref "R9") (pin "1") (pinfunction "1_1") (pintype "passive"))
      (node (ref "U9") (pin "8") (pinfunction "VDD_8") (pintype "power_in"))
    )
    (net (code "57") (name "W9-W10") (class "Default")
      (node (ref "SKIP3") (pin "2") (pinfunction "2_2") (pintype "passive"))
      (node (ref "U10") (pin "6") (pinfunction "DIN_6") (pintype "input"))
      (node (ref "U9") (pin "5") (pinfunction "DO_5") (pintype "output"))
    )
    (net (code "58") (name "W9B") (class "Default")
      (node (ref "O9") (pin "B") (pinfunction "B_B") (pintype "bidirectional"))
      (node (ref "U$19") (pin "3") (pinfunction "P$3_3") (pintype "bidirectional"))
      (node (ref "U$19") (pin "31") (pinfunction "P$3_31") (pintype "bidirectional"))
      (node (ref "U$19") (pin "32") (pinfunction "P$3_32") (pintype "bidirectional"))
      (node (ref "U$19") (pin "33") (pinfunction "P$3_33") (pintype "bidirectional"))
      (node (ref "U$19") (pin "3B") (pinfunction "P$3_3B") (pintype "bidirectional"))
      (node (ref "U9") (pin "3") (pinfunction "OUTB_3") (pintype "open_collector"))
    )
    (net (code "59") (name "W9G") (class "Default")
      (node (ref "O9") (pin "G") (pinfunction "G_G") (pintype "bidirectional"))
      (node (ref "U$19") (pin "2") (pinfunction "P$2_2") (pintype "bidirectional"))
      (node (ref "U$19") (pin "21") (pinfunction "P$2_21") (pintype "bidirectional"))
      (node (ref "U$19") (pin "22") (pinfunction "P$2_22") (pintype "bidirectional"))
      (node (ref "U$19") (pin "23") (pinfunction "P$2_23") (pintype "bidirectional"))
      (node (ref "U$19") (pin "2B") (pinfunction "P$2_2B") (pintype "bidirectional"))
      (node (ref "U9") (pin "1") (pinfunction "OUTG_1") (pintype "open_collector"))
    )
    (net (code "60") (name "W9R") (class "Default")
      (node (ref "O9") (pin "R") (pinfunction "R_R") (pintype "bidirectional"))
      (node (ref "U$19") (pin "1") (pinfunction "P$1_1") (pintype "bidirectional"))
      (node (ref "U$19") (pin "11") (pinfunction "P$1_11") (pintype "bidirectional"))
      (node (ref "U$19") (pin "12") (pinfunction "P$1_12") (pintype "bidirectional"))
      (node (ref "U$19") (pin "13") (pinfunction "P$1_13") (pintype "bidirectional"))
      (node (ref "U$19") (pin "1B") (pinfunction "P$1_1B") (pintype "bidirectional"))
      (node (ref "U9") (pin "2") (pinfunction "OUTR_2") (pintype "open_collector"))
    )
    (net (code "61") (name "W10-VCC") (class "Default")
      (node (ref "C10") (pin "1") (pinfunction "1_1") (pintype "passive"))
      (node (ref "R10") (pin "1") (pinfunction "1_1") (pintype "passive"))
      (node (ref "U10") (pin "8") (pinfunction "VDD_8") (pintype "power_in"))
    )
    (net (code "62") (name "W10B") (class "Default")
      (node (ref "O10") (pin "B") (pinfunction "B_B") (pintype "bidirectional"))
      (node (ref "U$20") (pin "4") (pinfunction "P$4_4") (pintype "bidirectional"))
      (node (ref "U$20") (pin "41") (pinfunction "P$4_41") (pintype "bidirectional"))
      (node (ref "U$20") (pin "42") (pinfunction "P$4_42") (pintype "bidirectional"))
      (node (ref "U$20") (pin "43") (pinfunction "P$4_43") (pintype "bidirectional"))
      (node (ref "U$20") (pin "4B") (pinfunction "P$4_4B") (pintype "bidirectional"))
      (node (ref "U10") (pin "3") (pinfunction "OUTB_3") (pintype "open_collector"))
    )
    (net (code "63") (name "W10G") (class "Default")
      (node (ref "O10") (pin "G") (pinfunction "G_G") (pintype "bidirectional"))
      (node (ref "U$20") (pin "3") (pinfunction "P$3_3") (pintype "bidirectional"))
      (node (ref "U$20") (pin "31") (pinfunction "P$3_31") (pintype "bidirectional"))
      (node (ref "U$20") (pin "32") (pinfunction "P$3_32") (pintype "bidirectional"))
      (node (ref "U$20") (pin "33") (pinfunction "P$3_33") (pintype "bidirectional"))
      (node (ref "U$20") (pin "3B") (pinfunction "P$3_3B") (pintype "bidirectional"))
      (node (ref "U10") (pin "1") (pinfunction "OUTG_1") (pintype "open_collector"))
    )
    (net (code "64") (name "W10R") (class "Default")
      (node (ref "O10") (pin "R") (pinfunction "R_R") (pintype "bidirectional"))
      (node (ref "U$20") (pin "2") (pinfunction "P$2_2") (pintype "bidirectional"))
      (node (ref "U$20") (pin "21") (pinfunction "P$2_21") (pintype "bidirectional"))
      (node (ref "U$20") (pin "22") (pinfunction "P$2_22") (pintype "bidirectional"))
      (node (ref "U$20") (pin "23") (pinfunction "P$2_23") (pintype "bidirectional"))
      (node (ref "U$20") (pin "2B") (pinfunction "P$2_2B") (pintype "bidirectional"))
      (node (ref "U10") (pin "2") (pinfunction "OUTR_2") (pintype "open_collector"))
    )
    (net (code "65") (name "unconnected-(U1-SET-Pad7)") (class "Default")
      (node (ref "U1") (pin "7") (pinfunction "SET_7") (pintype "bidirectional"))
    )
    (net (code "66") (name "unconnected-(U2-SET-Pad7)") (class "Default")
      (node (ref "U2") (pin "7") (pinfunction "SET_7") (pintype "bidirectional"))
    )
    (net (code "67") (name "unconnected-(U3-SET-Pad7)") (class "Default")
      (node (ref "U3") (pin "7") (pinfunction "SET_7") (pintype "bidirectional"))
    )
    (net (code "68") (name "unconnected-(U4-SET-Pad7)") (class "Default")
      (node (ref "U4") (pin "7") (pinfunction "SET_7") (pintype "bidirectional"))
    )
    (net (code "69") (name "unconnected-(U5-SET-Pad7)") (class "Default")
      (node (ref "U5") (pin "7") (pinfunction "SET_7") (pintype "bidirectional"))
    )
    (net (code "70") (name "unconnected-(U6-SET-Pad7)") (class "Default")
      (node (ref "U6") (pin "7") (pinfunction "SET_7") (pintype "bidirectional"))
    )
    (net (code "71") (name "unconnected-(U7-SET-Pad7)") (class "Default")
      (node (ref "U7") (pin "7") (pinfunction "SET_7") (pintype "bidirectional"))
    )
    (net (code "72") (name "unconnected-(U8-SET-Pad7)") (class "Default")
      (node (ref "U8") (pin "7") (pinfunction "SET_7") (pintype "bidirectional"))
    )
    (net (code "73") (name "unconnected-(U9-SET-Pad7)") (class "Default")
      (node (ref "U9") (pin "7") (pinfunction "SET_7") (pintype "bidirectional"))
    )
    (net (code "74") (name "unconnected-(U10-SET-Pad7)") (class "Default")
      (node (ref "U10") (pin "7") (pinfunction "SET_7") (pintype "bidirectional"))
    )
  )
)
